# MTP10.net
KiCad netlist of a schematic drawn in Altium Designer
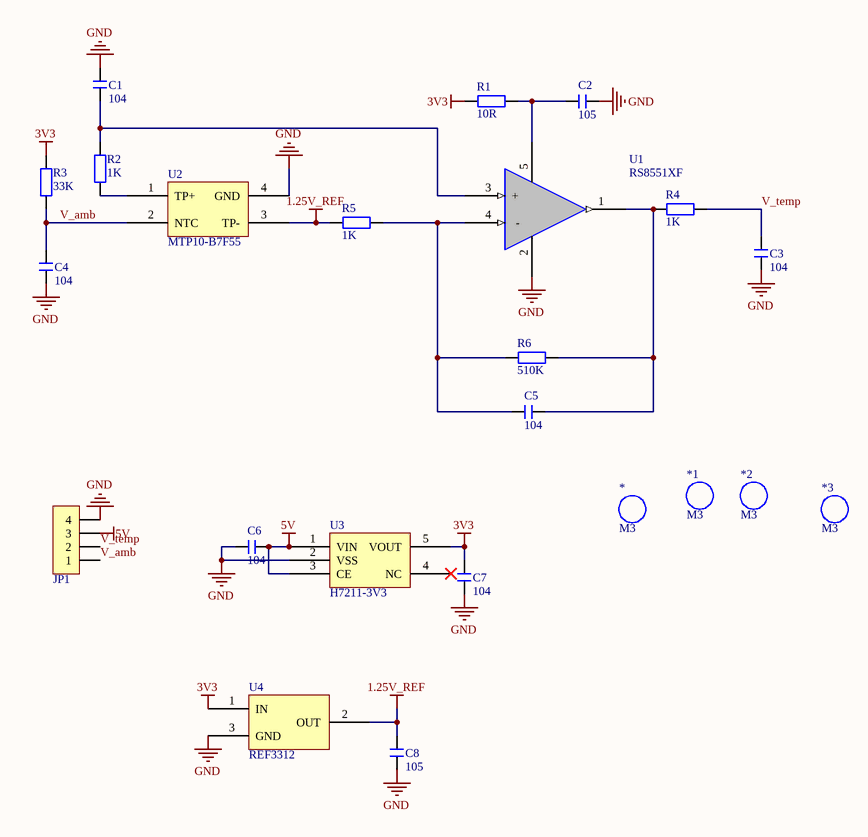
[diagram p0: MTP10.SchDoc]

(export (version "E")
  (design (tool "Eeschema 10.0.6"))
  (components
    (comp (ref "*")
      (value "M3")
      (footprint "M3 125X200")
      (description "铜柱孔")
      (fields (field (name "版权归属") "源创客"))
      (libsource (lib "15.1 - 未分类器件") (part "M3"))
    )
    (comp (ref "*1")
      (value "M3")
      (footprint "M3 125X200")
      (description "铜柱孔")
      (fields (field (name "版权归属") "源创客"))
      (libsource (lib "15.1 - 未分类器件") (part "M3"))
    )
    (comp (ref "*2")
      (value "M3")
      (footprint "M3 125X200")
      (description "铜柱孔")
      (fields (field (name "版权归属") "源创客"))
      (libsource (lib "15.1 - 未分类器件") (part "M3"))
    )
    (comp (ref "*3")
      (value "M3")
      (footprint "M3 125X200")
      (description "铜柱孔")
      (fields (field (name "版权归属") "源创客"))
      (libsource (lib "15.1 - 未分类器件") (part "M3"))
    )
    (comp (ref "C1")
      (value "104")
      (footprint "C 0603_L")
      (description "无极性贴片电容")
      (fields (field (name "版权归属") "源创客"))
      (libsource (lib "3.1   - 电阻-电容-电感") (part "C"))
    )
    (comp (ref "C2")
      (value "105")
      (footprint "C 0603_L")
      (description "无极性贴片电容")
      (fields (field (name "版权归属") "源创客"))
      (libsource (lib "3.1   - 电阻-电容-电感") (part "C"))
    )
    (comp (ref "C3")
      (value "104")
      (footprint "C 0603_L")
      (description "无极性贴片电容")
      (fields (field (name "版权归属") "源创客"))
      (libsource (lib "3.1   - 电阻-电容-电感") (part "C"))
    )
    (comp (ref "C4")
      (value "104")
      (footprint "C 0603_L")
      (description "无极性贴片电容")
      (fields (field (name "版权归属") "源创客"))
      (libsource (lib "3.1   - 电阻-电容-电感") (part "C"))
    )
    (comp (ref "C5")
      (value "104")
      (footprint "C 0603_L")
      (description "无极性贴片电容")
      (fields (field (name "版权归属") "源创客"))
      (libsource (lib "3.1   - 电阻-电容-电感") (part "C"))
    )
    (comp (ref "C6")
      (value "104")
      (footprint "C 0603_L")
      (description "无极性贴片电容")
      (fields (field (name "版权归属") "源创客"))
      (libsource (lib "3.1   - 电阻-电容-电感") (part "C"))
    )
    (comp (ref "C7")
      (value "104")
      (footprint "C 0603_L")
      (description "无极性贴片电容")
      (fields (field (name "版权归属") "源创客"))
      (libsource (lib "3.1   - 电阻-电容-电感") (part "C"))
    )
    (comp (ref "C8")
      (value "105")
      (footprint "C 0603_L")
      (description "无极性贴片电容")
      (fields (field (name "版权归属") "源创客"))
      (libsource (lib "3.1   - 电阻-电容-电感") (part "C"))
    )
    (comp (ref "JP1")
      (value "HDR-1X4")
      (footprint "HDR2.54-LI-4P")
      (description "4P接插件")
      (fields (field (name "版权归属") "源创客"))
      (libsource (lib "4.5   - 接插件-脚距2.54") (part "Header 4"))
    )
    (comp (ref "R1")
      (value "10R")
      (footprint "R 0603_L")
      (description "贴片电阻")
      (fields (field (name "版权归属") "源创客"))
      (libsource (lib "3.1   - 电阻-电容-电感") (part "R"))
    )
    (comp (ref "R2")
      (value "1K")
      (footprint "R 0603_L")
      (description "贴片电阻")
      (fields (field (name "版权归属") "源创客"))
      (libsource (lib "3.1   - 电阻-电容-电感") (part "R"))
    )
    (comp (ref "R3")
      (value "33K")
      (footprint "R 0603_L")
      (description "贴片电阻")
      (fields (field (name "版权归属") "源创客"))
      (libsource (lib "3.1   - 电阻-电容-电感") (part "R"))
    )
    (comp (ref "R4")
      (value "1K")
      (footprint "R 0603_L")
      (description "贴片电阻")
      (fields (field (name "版权归属") "源创客"))
      (libsource (lib "3.1   - 电阻-电容-电感") (part "R"))
    )
    (comp (ref "R5")
      (value "1K")
      (footprint "R 0603_L")
      (description "贴片电阻")
      (fields (field (name "版权归属") "源创客"))
      (libsource (lib "3.1   - 电阻-电容-电感") (part "R"))
    )
    (comp (ref "R6")
      (value "510K")
      (footprint "R 0603_L")
      (description "贴片电阻")
      (fields (field (name "版权归属") "源创客"))
      (libsource (lib "3.1   - 电阻-电容-电感") (part "R"))
    )
    (comp (ref "U1")
      (value "RS8551XF")
      (footprint "SOT23-5M")
      (description "仪表放大器")
      (libsource (lib "MTP10") (part "RS8551XF"))
    )
    (comp (ref "U2")
      (value "MTP10-B7F55")
      (footprint "MTP-10B")
      (description "MEMS 热电堆芯片")
      (libsource (lib "MTP10") (part "MTP10-B7F55"))
    )
    (comp (ref "U3")
      (value "H7211-3V3")
      (footprint "SOT23-5")
      (description "低噪声LDO")
      (libsource (lib "LMT70") (part "H7211"))
    )
    (comp (ref "U4")
      (value "REF3312")
      (footprint "SOT23-3L")
      (description "电压基准")
      (libsource (lib "MTP10") (part "REF33XX"))
    )
  )
  (nets
    (net (code "1") (name "/V_amb") (class "Default")
      (node (ref "C4") (pin "2") (pinfunction "2_2") (pintype "passive"))
      (node (ref "JP1") (pin "1") (pinfunction "1_1") (pintype "passive"))
      (node (ref "R3") (pin "1") (pinfunction "1_1") (pintype "passive"))
      (node (ref "U2") (pin "2") (pinfunction "NTC_2") (pintype "passive"))
    )
    (net (code "2") (name "/V_temp") (class "Default")
      (node (ref "C3") (pin "2") (pinfunction "2_2") (pintype "passive"))
      (node (ref "JP1") (pin "2") (pinfunction "2_2") (pintype "passive"))
      (node (ref "R4") (pin "1") (pinfunction "1_1") (pintype "passive"))
    )
    (net (code "3") (name "1.25V_REF") (class "Default")
      (node (ref "C8") (pin "2") (pinfunction "2_2") (pintype "passive"))
      (node (ref "R5") (pin "2") (pinfunction "2_2") (pintype "passive"))
      (node (ref "U2") (pin "3") (pinfunction "TP-_3") (pintype "passive"))
      (node (ref "U4") (pin "2") (pinfunction "OUT_2") (pintype "passive"))
    )
    (net (code "4") (name "3V3") (class "Default")
      (node (ref "C7") (pin "2") (pinfunction "2_2") (pintype "passive"))
      (node (ref "R1") (pin "2") (pinfunction "2_2") (pintype "passive"))
      (node (ref "R3") (pin "2") (pinfunction "2_2") (pintype "passive"))
      (node (ref "U3") (pin "5") (pinfunction "VOUT_5") (pintype "passive"))
      (node (ref "U4") (pin "1") (pinfunction "IN_1") (pintype "passive"))
    )
    (net (code "5") (name "5V") (class "Default")
      (node (ref "C6") (pin "1") (pinfunction "1_1") (pintype "passive"))
      (node (ref "JP1") (pin "3") (pinfunction "3_3") (pintype "passive"))
      (node (ref "U3") (pin "1") (pinfunction "VIN_1") (pintype "passive"))
      (node (ref "U3") (pin "3") (pinfunction "CE_3") (pintype "passive"))
    )
    (net (code "6") (name "GND") (class "Default")
      (node (ref "C1") (pin "1") (pinfunction "1_1") (pintype "passive"))
      (node (ref "C2") (pin "2") (pinfunction "2_2") (pintype "passive"))
      (node (ref "C3") (pin "1") (pinfunction "1_1") (pintype "passive"))
      (node (ref "C4") (pin "1") (pinfunction "1_1") (pintype "passive"))
      (node (ref "C6") (pin "2") (pinfunction "2_2") (pintype "passive"))
      (node (ref "C7") (pin "1") (pinfunction "1_1") (pintype "passive"))
      (node (ref "C8") (pin "1") (pinfunction "1_1") (pintype "passive"))
      (node (ref "JP1") (pin "4") (pinfunction "4_4") (pintype "passive"))
      (node (ref "U1") (pin "2") (pinfunction "GND_2") (pintype "power_in"))
      (node (ref "U2") (pin "4") (pinfunction "GND_4") (pintype "passive"))
      (node (ref "U3") (pin "2") (pinfunction "VSS_2") (pintype "passive"))
      (node (ref "U4") (pin "3") (pinfunction "GND_3") (pintype "passive"))
    )
    (net (code "7") (name "Net-(U1-+)") (class "Default")
      (node (ref "C1") (pin "2") (pinfunction "2_2") (pintype "passive"))
      (node (ref "R2") (pin "2") (pinfunction "2_2") (pintype "passive"))
      (node (ref "U1") (pin "3") (pinfunction "+_3") (pintype "input"))
    )
    (net (code "8") (name "Net-(U1-OUT)") (class "Default")
      (node (ref "C5") (pin "2") (pinfunction "2_2") (pintype "passive"))
      (node (ref "R4") (pin "2") (pinfunction "2_2") (pintype "passive"))
      (node (ref "R6") (pin "1") (pinfunction "1_1") (pintype "passive"))
      (node (ref "U1") (pin "1") (pinfunction "OUT_1") (pintype "output"))
    )
    (net (code "9") (name "Net-(U1-VDD)") (class "Default")
      (node (ref "C2") (pin "1") (pinfunction "1_1") (pintype "passive"))
      (node (ref "R1") (pin "1") (pinfunction "1_1") (pintype "passive"))
      (node (ref "U1") (pin "5") (pinfunction "VDD_5") (pintype "power_in"))
    )
    (net (code "10") (name "Net-(U1-－)") (class "Default")
      (node (ref "C5") (pin "1") (pinfunction "1_1") (pintype "passive"))
      (node (ref "R5") (pin "1") (pinfunction "1_1") (pintype "passive"))
      (node (ref "R6") (pin "2") (pinfunction "2_2") (pintype "passive"))
      (node (ref "U1") (pin "4") (pinfunction "－_4") (pintype "input"))
    )
    (net (code "11") (name "Net-(U2-TP+)") (class "Default")
      (node (ref "R2") (pin "1") (pinfunction "1_1") (pintype "passive"))
      (node (ref "U2") (pin "1") (pinfunction "TP+_1") (pintype "passive"))
    )
    (net (code "12") (name "unconnected-(U3-NC-Pad4)") (class "Default")
      (node (ref "U3") (pin "4") (pinfunction "NC_4") (pintype "passive+no_connect"))
    )
  )
)
